# ADF4351.net
KiCad netlist of a schematic drawn in Altium Designer
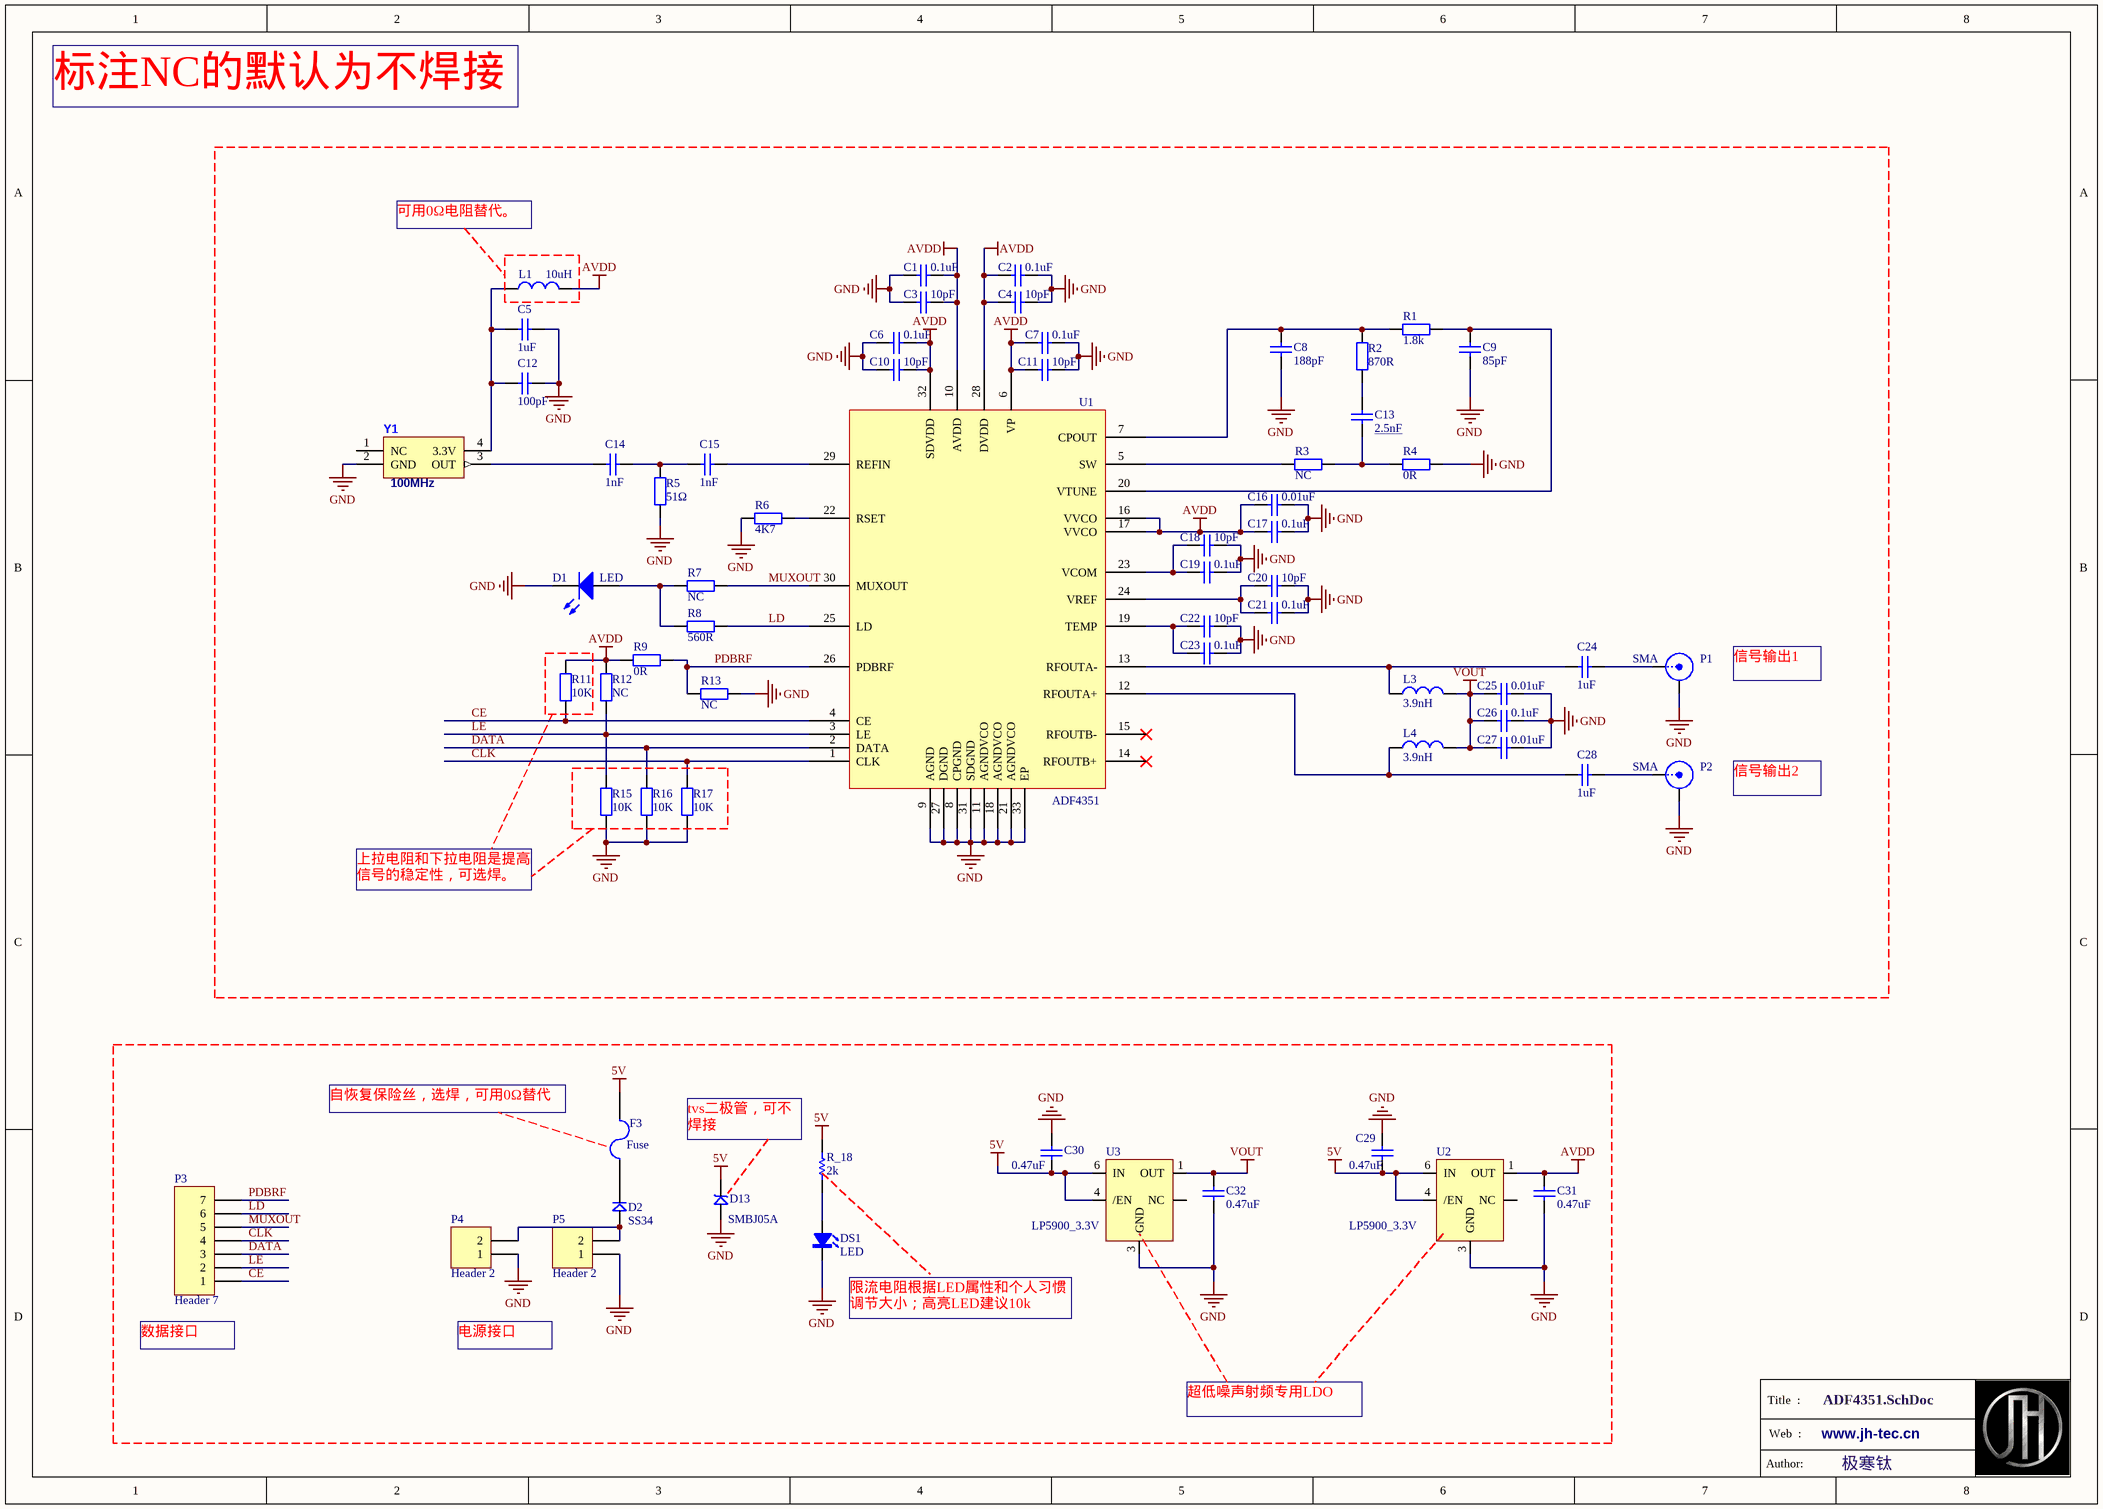
[diagram p0: ADF4351.SchDoc]

(export (version "E")
  (design (tool "Eeschema 10.0.6"))
  (components
    (comp (ref "C1")
      (value "0.1uF")
      (footprint "常用PCB:0603R")
      (description "Unpolar Capacitor")
      (libsource (lib "X_zqk") (part "C"))
    )
    (comp (ref "C2")
      (value "0.1uF")
      (footprint "常用PCB:0603R")
      (description "Unpolar Capacitor")
      (libsource (lib "X_zqk") (part "C"))
    )
    (comp (ref "C3")
      (value "10pF")
      (footprint "常用PCB:0603R")
      (description "Unpolar Capacitor")
      (libsource (lib "X_zqk") (part "C"))
    )
    (comp (ref "C4")
      (value "10pF")
      (footprint "常用PCB:0603R")
      (description "Unpolar Capacitor")
      (libsource (lib "X_zqk") (part "C"))
    )
    (comp (ref "C5")
      (value "1uF")
      (footprint "常用PCB:0603R")
      (description "Unpolar Capacitor")
      (libsource (lib "X_zqk") (part "C"))
    )
    (comp (ref "C6")
      (value "0.1uF")
      (footprint "常用PCB:0603R")
      (description "Unpolar Capacitor")
      (libsource (lib "X_zqk") (part "C"))
    )
    (comp (ref "C7")
      (value "0.1uF")
      (footprint "常用PCB:0603R")
      (description "Unpolar Capacitor")
      (libsource (lib "X_zqk") (part "C"))
    )
    (comp (ref "C8")
      (value "188pF")
      (footprint "常用PCB:0603R")
      (description "Unpolar Capacitor")
      (libsource (lib "X_zqk") (part "C"))
    )
    (comp (ref "C9")
      (value "85pF")
      (footprint "常用PCB:0603R")
      (description "Unpolar Capacitor")
      (libsource (lib "X_zqk") (part "C"))
    )
    (comp (ref "C10")
      (value "10pF")
      (footprint "常用PCB:0603R")
      (description "Unpolar Capacitor")
      (libsource (lib "X_zqk") (part "C"))
    )
    (comp (ref "C11")
      (value "10pF")
      (footprint "常用PCB:0603R")
      (description "Unpolar Capacitor")
      (libsource (lib "X_zqk") (part "C"))
    )
    (comp (ref "C12")
      (value "100pF")
      (footprint "常用PCB:0603R")
      (description "Unpolar Capacitor")
      (libsource (lib "X_zqk") (part "C"))
    )
    (comp (ref "C13")
      (value "2.5nF")
      (footprint "常用PCB:0603R")
      (description "Unpolar Capacitor")
      (libsource (lib "X_zqk") (part "C"))
    )
    (comp (ref "C14")
      (value "1nF")
      (footprint "常用PCB:0603R")
      (description "Unpolar Capacitor")
      (libsource (lib "X_zqk") (part "C"))
    )
    (comp (ref "C15")
      (value "1nF")
      (footprint "常用PCB:0603R")
      (description "Unpolar Capacitor")
      (libsource (lib "X_zqk") (part "C"))
    )
    (comp (ref "C16")
      (value "0.01uF")
      (footprint "常用PCB:0603R")
      (description "Unpolar Capacitor")
      (libsource (lib "X_zqk") (part "C"))
    )
    (comp (ref "C17")
      (value "0.1uF")
      (footprint "常用PCB:0603R")
      (description "Unpolar Capacitor")
      (libsource (lib "X_zqk") (part "C"))
    )
    (comp (ref "C18")
      (value "10pF")
      (footprint "常用PCB:0603R")
      (description "Unpolar Capacitor")
      (libsource (lib "X_zqk") (part "C"))
    )
    (comp (ref "C19")
      (value "0.1uF")
      (footprint "常用PCB:0603R")
      (description "Unpolar Capacitor")
      (libsource (lib "X_zqk") (part "C"))
    )
    (comp (ref "C20")
      (value "10pF")
      (footprint "常用PCB:0603R")
      (description "Unpolar Capacitor")
      (libsource (lib "X_zqk") (part "C"))
    )
    (comp (ref "C21")
      (value "0.1uF")
      (footprint "常用PCB:0603R")
      (description "Unpolar Capacitor")
      (libsource (lib "X_zqk") (part "C"))
    )
    (comp (ref "C22")
      (value "10pF")
      (footprint "常用PCB:0603R")
      (description "Unpolar Capacitor")
      (libsource (lib "X_zqk") (part "C"))
    )
    (comp (ref "C23")
      (value "0.1uF")
      (footprint "常用PCB:0603R")
      (description "Unpolar Capacitor")
      (libsource (lib "X_zqk") (part "C"))
    )
    (comp (ref "C24")
      (value "1uF")
      (footprint "常用PCB:0603R")
      (description "Unpolar Capacitor")
      (libsource (lib "X_zqk") (part "C"))
    )
    (comp (ref "C25")
      (value "0.01uF")
      (footprint "常用PCB:0603R")
      (description "Unpolar Capacitor")
      (libsource (lib "X_zqk") (part "C"))
    )
    (comp (ref "C26")
      (value "0.1uF")
      (footprint "常用PCB:0603R")
      (description "Unpolar Capacitor")
      (libsource (lib "X_zqk") (part "C"))
    )
    (comp (ref "C27")
      (value "0.01uF")
      (footprint "常用PCB:0603R")
      (description "Unpolar Capacitor")
      (libsource (lib "X_zqk") (part "C"))
    )
    (comp (ref "C28")
      (value "1uF")
      (footprint "常用PCB:0603R")
      (description "Unpolar Capacitor")
      (libsource (lib "X_zqk") (part "C"))
    )
    (comp (ref "C29") (value "0.47uF") (footprint "常用PCB:0603R") (libsource (lib "常用sch") (part "cap")))
    (comp (ref "C30") (value "0.47uF") (footprint "常用PCB:0603R") (libsource (lib "常用sch") (part "cap")))
    (comp (ref "C31") (value "0.47uF") (footprint "常用PCB:0603R") (libsource (lib "常用sch") (part "cap")))
    (comp (ref "C32") (value "0.47uF") (footprint "常用PCB:0603R") (libsource (lib "常用sch") (part "cap")))
    (comp (ref "D1") (value "LED") (footprint "常用PCB:0603_LED") (libsource (lib "X_zqk") (part "LED_0603")))
    (comp (ref "D2")
      (value "SS34")
      (footprint "常用PCB:SS34")
      (description "1N4148")
      (libsource (lib "常用sch") (part "D"))
    )
    (comp (ref "D13")
      (value "SMBJ05A")
      (footprint "SMBJ")
      (description "TVS")
      (libsource (lib "ATK-SIM900A") (part "SMBJ"))
    )
    (comp (ref "DS1") (value "LED") (footprint "常用PCB:0603_LED") (libsource (lib "常用sch") (part "LED")))
    (comp (ref "F3")
      (value "Fuse")
      (footprint "常用PCB:0805+")
      (fields (field (name "PUBLISHER") "Altium Limited"))
      (libsource (lib "Miscellaneous Devices") (part "Fuse 2"))
    )
    (comp (ref "L1") (value "10uH") (footprint "常用PCB:0603R") (libsource (lib "X_zqk") (part "INDUCTOR")))
    (comp (ref "L3") (value "3.9nH") (footprint "常用PCB:0603R") (libsource (lib "X_zqk") (part "INDUCTOR")))
    (comp (ref "L4") (value "3.9nH") (footprint "常用PCB:0603R") (libsource (lib "X_zqk") (part "INDUCTOR")))
    (comp (ref "P1")
      (value "SMA")
      (footprint "常用PCB:SMA_3D")
      (description "Port for HF signal")
      (libsource (lib "X_zqk") (part "SMA"))
    )
    (comp (ref "P2")
      (value "SMA")
      (footprint "常用PCB:SMA_3D")
      (description "Port for HF signal")
      (libsource (lib "X_zqk") (part "SMA"))
    )
    (comp (ref "P3")
      (value "Header 7")
      (footprint "3D:HDR1X7")
      (description "Header, 7-Pin")
      (fields (field (name "PUBLISHER") "Altium Limited"))
      (libsource (lib "Miscellaneous Connectors") (part "Header 7"))
    )
    (comp (ref "P4")
      (value "Header 2")
      (footprint "DC2")
      (description "Header, 2-Pin")
      (fields (field (name "PUBLISHER") "*"))
      (libsource (lib "常用sch") (part "Header 2"))
    )
    (comp (ref "P5")
      (value "Header 2")
      (footprint "3D:HDR1X2")
      (description "Header, 2-Pin")
      (fields (field (name "PUBLISHER") "*"))
      (libsource (lib "常用sch") (part "Header 2"))
    )
    (comp (ref "R1")
      (value "1.8k")
      (footprint "常用PCB:0603R")
      (description "Resister")
      (libsource (lib "") (part "R_1"))
    )
    (comp (ref "R2")
      (value "870R")
      (footprint "常用PCB:0603R")
      (description "Resister")
      (libsource (lib "") (part "R_2"))
    )
    (comp (ref "R3")
      (value "NC")
      (footprint "常用PCB:0603R")
      (description "Resister")
      (libsource (lib "") (part "R_1"))
    )
    (comp (ref "R4")
      (value "0R")
      (footprint "常用PCB:0603R")
      (description "Resister")
      (libsource (lib "") (part "R_1"))
    )
    (comp (ref "R5")
      (value "51Ω")
      (footprint "常用PCB:0603R")
      (description "Resister")
      (libsource (lib "X_zqk") (part "R"))
    )
    (comp (ref "R6")
      (value "4K7")
      (footprint "常用PCB:0603R")
      (description "Resister")
      (libsource (lib "") (part "R_3"))
    )
    (comp (ref "R7")
      (value "NC")
      (footprint "常用PCB:0603R")
      (description "Resister")
      (libsource (lib "") (part "R_1"))
    )
    (comp (ref "R8")
      (value "560R")
      (footprint "常用PCB:0603R")
      (description "Resister")
      (libsource (lib "") (part "R_1"))
    )
    (comp (ref "R9")
      (value "0R")
      (footprint "常用PCB:0603R")
      (description "Resister")
      (libsource (lib "") (part "R_1"))
    )
    (comp (ref "R11")
      (value "10K")
      (footprint "常用PCB:0603R")
      (description "Resister")
      (libsource (lib "X_zqk") (part "R"))
    )
    (comp (ref "R12")
      (value "NC")
      (footprint "常用PCB:0603R")
      (description "Resister")
      (libsource (lib "X_zqk") (part "R"))
    )
    (comp (ref "R13")
      (value "NC")
      (footprint "常用PCB:0603R")
      (description "Resister")
      (libsource (lib "") (part "R_1"))
    )
    (comp (ref "R15")
      (value "10K")
      (footprint "常用PCB:0603R")
      (description "Resister")
      (libsource (lib "X_zqk") (part "R"))
    )
    (comp (ref "R16")
      (value "10K")
      (footprint "常用PCB:0603R")
      (description "Resister")
      (libsource (lib "X_zqk") (part "R"))
    )
    (comp (ref "R17")
      (value "10K")
      (footprint "常用PCB:0603R")
      (description "Resister")
      (libsource (lib "X_zqk") (part "R"))
    )
    (comp (ref "R_18") (value "2k") (footprint "常用PCB:0603R") (libsource (lib "常用sch") (part "RES0805")))
    (comp (ref "U1")
      (value "ADF4351")
      (footprint "3D:ADF4351")
      (description "Wideband Synthesizer with Integrated VCO")
      (libsource (lib "常用sch") (part "ADF4351BCPZ"))
    )
    (comp (ref "U2")
      (value "LP5900_3.3V")
      (footprint "常用PCB:WSON_6")
      (libsource (lib "常用sch") (part "lp5900"))
    )
    (comp (ref "U3")
      (value "LP5900_3.3V")
      (footprint "常用PCB:WSON_6")
      (libsource (lib "常用sch") (part "lp5900"))
    )
    (comp (ref "Y1")
      (value "100MHz")
      (footprint "X3225")
      (description "XTAL")
      (libsource (lib "*") (part "XTALCOSC"))
    )
  )
  (nets
    (net (code "1") (name "/CE") (class "Default")
      (node (ref "P3") (pin "1") (pinfunction "1_1") (pintype "passive"))
      (node (ref "R11") (pin "1") (pinfunction "1_1") (pintype "passive"))
      (node (ref "U1") (pin "4") (pinfunction "CE_4") (pintype "passive"))
    )
    (net (code "2") (name "/CLK") (class "Default")
      (node (ref "P3") (pin "4") (pinfunction "4_4") (pintype "passive"))
      (node (ref "R17") (pin "2") (pinfunction "2_2") (pintype "passive"))
      (node (ref "U1") (pin "1") (pinfunction "CLK_1") (pintype "passive"))
    )
    (net (code "3") (name "/DATA") (class "Default")
      (node (ref "P3") (pin "3") (pinfunction "3_3") (pintype "passive"))
      (node (ref "R16") (pin "2") (pinfunction "2_2") (pintype "passive"))
      (node (ref "U1") (pin "2") (pinfunction "DATA_2") (pintype "passive"))
    )
    (net (code "4") (name "/LD") (class "Default")
      (node (ref "P3") (pin "6") (pinfunction "6_6") (pintype "passive"))
      (node (ref "R8") (pin "2") (pinfunction "2_2") (pintype "passive"))
      (node (ref "U1") (pin "25") (pinfunction "LD_25") (pintype "passive"))
    )
    (net (code "5") (name "/LE") (class "Default")
      (node (ref "P3") (pin "2") (pinfunction "2_2") (pintype "passive"))
      (node (ref "R12") (pin "1") (pinfunction "1_1") (pintype "passive"))
      (node (ref "R15") (pin "2") (pinfunction "2_2") (pintype "passive"))
      (node (ref "U1") (pin "3") (pinfunction "LE_3") (pintype "passive"))
    )
    (net (code "6") (name "/MUXOUT") (class "Default")
      (node (ref "P3") (pin "5") (pinfunction "5_5") (pintype "passive"))
      (node (ref "R7") (pin "2") (pinfunction "2_2") (pintype "passive"))
      (node (ref "U1") (pin "30") (pinfunction "MUXOUT_30") (pintype "passive"))
    )
    (net (code "7") (name "/PDBRF") (class "Default")
      (node (ref "P3") (pin "7") (pinfunction "7_7") (pintype "passive"))
      (node (ref "R13") (pin "1") (pinfunction "1_1") (pintype "passive"))
      (node (ref "R9") (pin "2") (pinfunction "2_2") (pintype "passive"))
      (node (ref "U1") (pin "26") (pinfunction "PDBRF_26") (pintype "passive"))
    )
    (net (code "8") (name "5V") (class "Default")
      (node (ref "C29") (pin "1") (pinfunction "1_1") (pintype "passive"))
      (node (ref "C30") (pin "1") (pinfunction "1_1") (pintype "passive"))
      (node (ref "D13") (pin "2") (pintype "passive"))
      (node (ref "F3") (pin "1") (pinfunction "1_1") (pintype "passive"))
      (node (ref "R_18") (pin "1") (pinfunction "1_1") (pintype "passive"))
      (node (ref "U2") (pin "4") (pinfunction "/EN_4") (pintype "passive"))
      (node (ref "U2") (pin "6") (pinfunction "IN_6") (pintype "passive"))
      (node (ref "U3") (pin "4") (pinfunction "/EN_4") (pintype "passive"))
      (node (ref "U3") (pin "6") (pinfunction "IN_6") (pintype "passive"))
    )
    (net (code "9") (name "AVDD") (class "Default")
      (node (ref "C1") (pin "2") (pinfunction "2_2") (pintype "passive"))
      (node (ref "C10") (pin "2") (pinfunction "2_2") (pintype "passive"))
      (node (ref "C11") (pin "1") (pinfunction "1_1") (pintype "passive"))
      (node (ref "C16") (pin "1") (pinfunction "1_1") (pintype "passive"))
      (node (ref "C17") (pin "1") (pinfunction "1_1") (pintype "passive"))
      (node (ref "C2") (pin "1") (pinfunction "1_1") (pintype "passive"))
      (node (ref "C3") (pin "2") (pinfunction "2_2") (pintype "passive"))
      (node (ref "C31") (pin "1") (pinfunction "1_1") (pintype "passive"))
      (node (ref "C4") (pin "1") (pinfunction "1_1") (pintype "passive"))
      (node (ref "C6") (pin "2") (pinfunction "2_2") (pintype "passive"))
      (node (ref "C7") (pin "1") (pinfunction "1_1") (pintype "passive"))
      (node (ref "L1") (pin "2") (pinfunction "2_2") (pintype "passive"))
      (node (ref "R11") (pin "2") (pinfunction "2_2") (pintype "passive"))
      (node (ref "R12") (pin "2") (pinfunction "2_2") (pintype "passive"))
      (node (ref "R9") (pin "1") (pinfunction "1_1") (pintype "passive"))
      (node (ref "U1") (pin "10") (pinfunction "AVDD_10") (pintype "passive"))
      (node (ref "U1") (pin "16") (pinfunction "VVCO_16") (pintype "passive"))
      (node (ref "U1") (pin "17") (pinfunction "VVCO_17") (pintype "passive"))
      (node (ref "U1") (pin "28") (pinfunction "DVDD_28") (pintype "passive"))
      (node (ref "U1") (pin "32") (pinfunction "SDVDD_32") (pintype "passive"))
      (node (ref "U1") (pin "6") (pinfunction "VP_6") (pintype "passive"))
      (node (ref "U2") (pin "1") (pinfunction "OUT_1") (pintype "passive"))
    )
    (net (code "10") (name "GND") (class "Default")
      (node (ref "C1") (pin "1") (pinfunction "1_1") (pintype "passive"))
      (node (ref "C10") (pin "1") (pinfunction "1_1") (pintype "passive"))
      (node (ref "C11") (pin "2") (pinfunction "2_2") (pintype "passive"))
      (node (ref "C12") (pin "2") (pinfunction "2_2") (pintype "passive"))
      (node (ref "C16") (pin "2") (pinfunction "2_2") (pintype "passive"))
      (node (ref "C17") (pin "2") (pinfunction "2_2") (pintype "passive"))
      (node (ref "C18") (pin "2") (pinfunction "2_2") (pintype "passive"))
      (node (ref "C19") (pin "2") (pinfunction "2_2") (pintype "passive"))
      (node (ref "C2") (pin "2") (pinfunction "2_2") (pintype "passive"))
      (node (ref "C20") (pin "2") (pinfunction "2_2") (pintype "passive"))
      (node (ref "C21") (pin "2") (pinfunction "2_2") (pintype "passive"))
      (node (ref "C22") (pin "2") (pinfunction "2_2") (pintype "passive"))
      (node (ref "C23") (pin "2") (pinfunction "2_2") (pintype "passive"))
      (node (ref "C25") (pin "2") (pinfunction "2_2") (pintype "passive"))
      (node (ref "C26") (pin "2") (pinfunction "2_2") (pintype "passive"))
      (node (ref "C27") (pin "2") (pinfunction "2_2") (pintype "passive"))
      (node (ref "C29") (pin "2") (pinfunction "2_2") (pintype "passive"))
      (node (ref "C3") (pin "1") (pinfunction "1_1") (pintype "passive"))
      (node (ref "C30") (pin "2") (pinfunction "2_2") (pintype "passive"))
      (node (ref "C31") (pin "2") (pinfunction "2_2") (pintype "passive"))
      (node (ref "C32") (pin "2") (pinfunction "2_2") (pintype "passive"))
      (node (ref "C4") (pin "2") (pinfunction "2_2") (pintype "passive"))
      (node (ref "C5") (pin "2") (pinfunction "2_2") (pintype "passive"))
      (node (ref "C6") (pin "1") (pinfunction "1_1") (pintype "passive"))
      (node (ref "C7") (pin "2") (pinfunction "2_2") (pintype "passive"))
      (node (ref "C8") (pin "2") (pinfunction "2_2") (pintype "passive"))
      (node (ref "C9") (pin "2") (pinfunction "2_2") (pintype "passive"))
      (node (ref "D1") (pin "2") (pinfunction "2_2") (pintype "passive"))
      (node (ref "D13") (pin "1") (pintype "passive"))
      (node (ref "DS1") (pin "2") (pinfunction "2_2") (pintype "passive"))
      (node (ref "P1") (pin "2") (pinfunction "Y_2") (pintype "passive"))
      (node (ref "P2") (pin "2") (pinfunction "Y_2") (pintype "passive"))
      (node (ref "P4") (pin "1") (pinfunction "1_1") (pintype "passive"))
      (node (ref "P5") (pin "1") (pinfunction "1_1") (pintype "passive"))
      (node (ref "R13") (pin "2") (pinfunction "2_2") (pintype "passive"))
      (node (ref "R15") (pin "1") (pinfunction "1_1") (pintype "passive"))
      (node (ref "R16") (pin "1") (pinfunction "1_1") (pintype "passive"))
      (node (ref "R17") (pin "1") (pinfunction "1_1") (pintype "passive"))
      (node (ref "R4") (pin "2") (pinfunction "2_2") (pintype "passive"))
      (node (ref "R5") (pin "1") (pinfunction "1_1") (pintype "passive"))
      (node (ref "R6") (pin "2") (pinfunction "2_2") (pintype "passive"))
      (node (ref "U1") (pin "11") (pinfunction "AGNDVCO_11") (pintype "passive"))
      (node (ref "U1") (pin "18") (pinfunction "AGNDVCO_18") (pintype "passive"))
      (node (ref "U1") (pin "21") (pinfunction "AGNDVCO_21") (pintype "passive"))
      (node (ref "U1") (pin "27") (pinfunction "DGND_27") (pintype "passive"))
      (node (ref "U1") (pin "31") (pinfunction "SDGND_31") (pintype "passive"))
      (node (ref "U1") (pin "33") (pinfunction "EP_33") (pintype "passive"))
      (node (ref "U1") (pin "8") (pinfunction "CPGND_8") (pintype "passive"))
      (node (ref "U1") (pin "9") (pinfunction "AGND_9") (pintype "passive"))
      (node (ref "U2") (pin "3") (pinfunction "GND_3") (pintype "passive"))
      (node (ref "U3") (pin "3") (pinfunction "GND_3") (pintype "passive"))
      (node (ref "Y1") (pin "2") (pinfunction "GND_2") (pintype "power_in"))
    )
    (net (code "11") (name "Net-(C13-Pad1)") (class "Default")
      (node (ref "C13") (pin "1") (pinfunction "1_1") (pintype "passive"))
      (node (ref "R2") (pin "2") (pinfunction "2_2") (pintype "passive"))
    )
    (net (code "12") (name "Net-(C13-Pad2)") (class "Default")
      (node (ref "C13") (pin "2") (pinfunction "2_2") (pintype "passive"))
      (node (ref "R3") (pin "2") (pinfunction "2_2") (pintype "passive"))
      (node (ref "R4") (pin "1") (pinfunction "1_1") (pintype "passive"))
    )
    (net (code "13") (name "Net-(C14-Pad2)") (class "Default")
      (node (ref "C14") (pin "2") (pinfunction "2_2") (pintype "passive"))
      (node (ref "C15") (pin "1") (pinfunction "1_1") (pintype "passive"))
      (node (ref "R5") (pin "2") (pinfunction "2_2") (pintype "passive"))
    )
    (net (code "14") (name "Net-(D1-Pad1)") (class "Default")
      (node (ref "D1") (pin "1") (pinfunction "1_1") (pintype "passive"))
      (node (ref "R7") (pin "1") (pinfunction "1_1") (pintype "passive"))
      (node (ref "R8") (pin "1") (pinfunction "1_1") (pintype "passive"))
    )
    (net (code "15") (name "Net-(D2-Pad1)") (class "Default")
      (node (ref "D2") (pin "1") (pintype "passive"))
      (node (ref "P4") (pin "2") (pinfunction "2_2") (pintype "passive"))
      (node (ref "P5") (pin "2") (pinfunction "2_2") (pintype "passive"))
    )
    (net (code "16") (name "Net-(D2-Pad2)") (class "Default")
      (node (ref "D2") (pin "2") (pintype "passive"))
      (node (ref "F3") (pin "2") (pinfunction "2_2") (pintype "passive"))
    )
    (net (code "17") (name "Net-(DS1-Pad1)") (class "Default")
      (node (ref "DS1") (pin "1") (pinfunction "1_1") (pintype "passive"))
      (node (ref "R_18") (pin "2") (pinfunction "2_2") (pintype "passive"))
    )
    (net (code "18") (name "Net-(P1-X)") (class "Default")
      (node (ref "C24") (pin "2") (pinfunction "2_2") (pintype "passive"))
      (node (ref "P1") (pin "1") (pinfunction "X_1") (pintype "passive"))
    )
    (net (code "19") (name "Net-(P2-X)") (class "Default")
      (node (ref "C28") (pin "2") (pinfunction "2_2") (pintype "passive"))
      (node (ref "P2") (pin "1") (pinfunction "X_1") (pintype "passive"))
    )
    (net (code "20") (name "Net-(U1-CPOUT)") (class "Default")
      (node (ref "C8") (pin "1") (pinfunction "1_1") (pintype "passive"))
      (node (ref "R1") (pin "1") (pinfunction "1_1") (pintype "passive"))
      (node (ref "R2") (pin "1") (pinfunction "1_1") (pintype "passive"))
      (node (ref "U1") (pin "7") (pinfunction "CPOUT_7") (pintype "passive"))
    )
    (net (code "21") (name "Net-(U1-REFIN)") (class "Default")
      (node (ref "C15") (pin "2") (pinfunction "2_2") (pintype "passive"))
      (node (ref "U1") (pin "29") (pinfunction "REFIN_29") (pintype "passive"))
    )
    (net (code "22") (name "Net-(U1-RFOUTA+)") (class "Default")
      (node (ref "C28") (pin "1") (pinfunction "1_1") (pintype "passive"))
      (node (ref "L4") (pin "1") (pinfunction "1_1") (pintype "passive"))
      (node (ref "U1") (pin "12") (pinfunction "RFOUTA+_12") (pintype "passive"))
    )
    (net (code "23") (name "Net-(U1-RFOUTA-)") (class "Default")
      (node (ref "C24") (pin "1") (pinfunction "1_1") (pintype "passive"))
      (node (ref "L3") (pin "1") (pinfunction "1_1") (pintype "passive"))
      (node (ref "U1") (pin "13") (pinfunction "RFOUTA-_13") (pintype "passive"))
    )
    (net (code "24") (name "Net-(U1-RSET)") (class "Default")
      (node (ref "R6") (pin "1") (pinfunction "1_1") (pintype "passive"))
      (node (ref "U1") (pin "22") (pinfunction "RSET_22") (pintype "passive"))
    )
    (net (code "25") (name "Net-(U1-SW)") (class "Default")
      (node (ref "R3") (pin "1") (pinfunction "1_1") (pintype "passive"))
      (node (ref "U1") (pin "5") (pinfunction "SW_5") (pintype "passive"))
    )
    (net (code "26") (name "Net-(U1-TEMP)") (class "Default")
      (node (ref "C22") (pin "1") (pinfunction "1_1") (pintype "passive"))
      (node (ref "C23") (pin "1") (pinfunction "1_1") (pintype "passive"))
      (node (ref "U1") (pin "19") (pinfunction "TEMP_19") (pintype "passive"))
    )
    (net (code "27") (name "Net-(U1-VCOM)") (class "Default")
      (node (ref "C18") (pin "1") (pinfunction "1_1") (pintype "passive"))
      (node (ref "C19") (pin "1") (pinfunction "1_1") (pintype "passive"))
      (node (ref "U1") (pin "23") (pinfunction "VCOM_23") (pintype "passive"))
    )
    (net (code "28") (name "Net-(U1-VREF)") (class "Default")
      (node (ref "C20") (pin "1") (pinfunction "1_1") (pintype "passive"))
      (node (ref "C21") (pin "1") (pinfunction "1_1") (pintype "passive"))
      (node (ref "U1") (pin "24") (pinfunction "VREF_24") (pintype "passive"))
    )
    (net (code "29") (name "Net-(U1-VTUNE)") (class "Default")
      (node (ref "C9") (pin "1") (pinfunction "1_1") (pintype "passive"))
      (node (ref "R1") (pin "2") (pinfunction "2_2") (pintype "passive"))
      (node (ref "U1") (pin "20") (pinfunction "VTUNE_20") (pintype "passive"))
    )
    (net (code "30") (name "Net-(Y1-3.3V)") (class "Default")
      (node (ref "C12") (pin "1") (pinfunction "1_1") (pintype "passive"))
      (node (ref "C5") (pin "1") (pinfunction "1_1") (pintype "passive"))
      (node (ref "L1") (pin "1") (pinfunction "1_1") (pintype "passive"))
      (node (ref "Y1") (pin "4") (pinfunction "3.3V_4") (pintype "power_in"))
    )
    (net (code "31") (name "Net-(Y1-OUT)") (class "Default")
      (node (ref "C14") (pin "1") (pinfunction "1_1") (pintype "passive"))
      (node (ref "Y1") (pin "3") (pinfunction "OUT_3") (pintype "output"))
    )
    (net (code "32") (name "VOUT") (class "Default")
      (node (ref "C25") (pin "1") (pinfunction "1_1") (pintype "passive"))
      (node (ref "C26") (pin "1") (pinfunction "1_1") (pintype "passive"))
      (node (ref "C27") (pin "1") (pinfunction "1_1") (pintype "passive"))
      (node (ref "C32") (pin "1") (pinfunction "1_1") (pintype "passive"))
      (node (ref "L3") (pin "2") (pinfunction "2_2") (pintype "passive"))
      (node (ref "L4") (pin "2") (pinfunction "2_2") (pintype "passive"))
      (node (ref "U3") (pin "1") (pinfunction "OUT_1") (pintype "passive"))
    )
    (net (code "33") (name "unconnected-(U1-RFOUTB+-Pad14)") (class "Default")
      (node (ref "U1") (pin "14") (pinfunction "RFOUTB+_14") (pintype "passive+no_connect"))
    )
    (net (code "34") (name "unconnected-(U1-RFOUTB--Pad15)") (class "Default")
      (node (ref "U1") (pin "15") (pinfunction "RFOUTB-_15") (pintype "passive+no_connect"))
    )
    (net (code "35") (name "unconnected-(U2-NC-Pad4)") (class "Default")
      (node (ref "U2") (pin "4") (pinfunction "NC_4") (pintype "passive"))
    )
    (net (code "36") (name "unconnected-(U3-NC-Pad4)") (class "Default")
      (node (ref "U3") (pin "4") (pinfunction "NC_4") (pintype "passive"))
    )
    (net (code "37") (name "unconnected-(Y1-NC-Pad1)") (class "Default")
      (node (ref "Y1") (pin "1") (pinfunction "NC_1") (pintype "passive"))
    )
  )
)
